# AFE_Buffer.net
KiCad netlist of a schematic drawn in Altium Designer
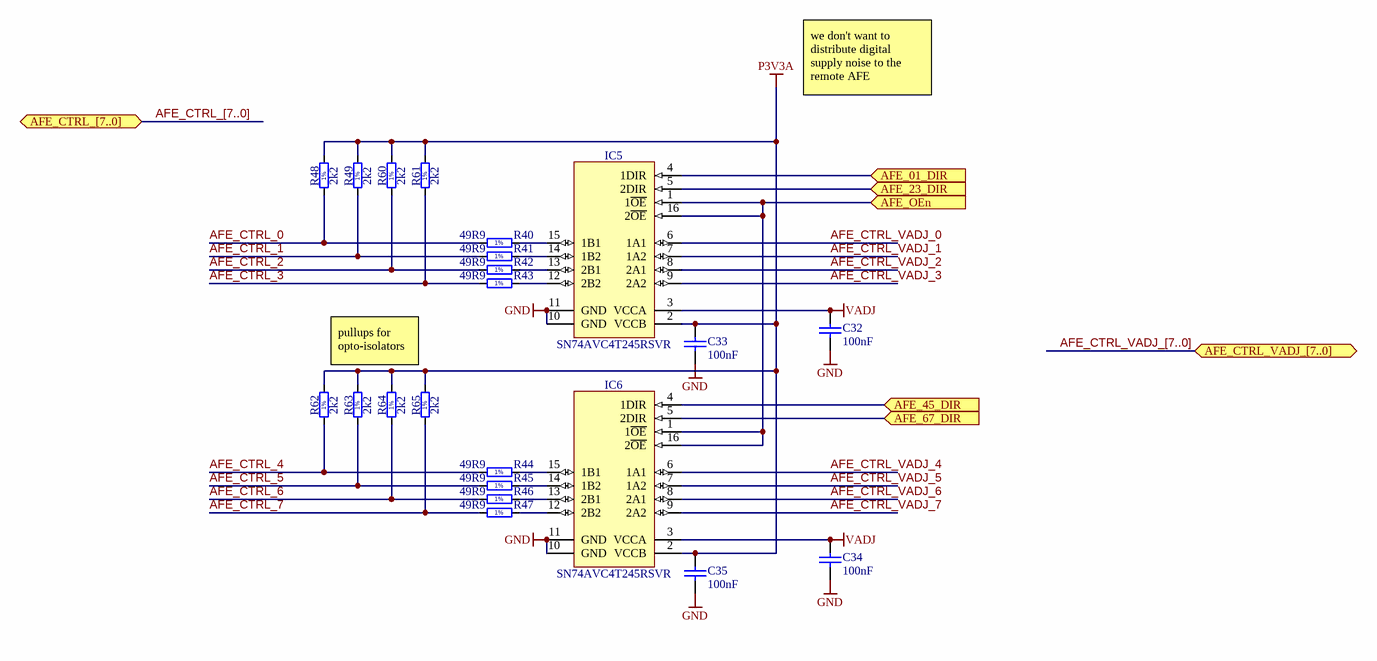
[diagram p0: AFE_Buffer.SchDoc]

(export (version "E")
  (design (tool "Eeschema 10.0.6"))
  (components
    (comp (ref "C32")
      (value "100nF")
      (footprint "CAPC1005X55N")
      (description "Non-polarised capacitor")
      (fields
        (field (name "PART NUMBER") "CC0402_100NF_16V_10%_X5R")
        (field (name "VOLTAGE") "16V")
        (field (name "AUTHOR") "CERN DEM JLC")
      )
      (libsource (lib "Capacitors") (part "Capacitor - non polarized"))
    )
    (comp (ref "C33")
      (value "100nF")
      (footprint "CAPC1005X55N")
      (description "Non-polarised capacitor")
      (fields
        (field (name "PART NUMBER") "CC0402_100NF_16V_10%_X5R")
        (field (name "VOLTAGE") "16V")
        (field (name "AUTHOR") "CERN DEM JLC")
      )
      (libsource (lib "Capacitors") (part "Capacitor - non polarized"))
    )
    (comp (ref "C34")
      (value "100nF")
      (footprint "CAPC1005X55N")
      (description "Non-polarised capacitor")
      (fields
        (field (name "PART NUMBER") "CC0402_100NF_16V_10%_X5R")
        (field (name "VOLTAGE") "16V")
        (field (name "AUTHOR") "CERN DEM JLC")
      )
      (libsource (lib "Capacitors") (part "Capacitor - non polarized"))
    )
    (comp (ref "C35")
      (value "100nF")
      (footprint "CAPC1005X55N")
      (description "Non-polarised capacitor")
      (fields
        (field (name "PART NUMBER") "CC0402_100NF_16V_10%_X5R")
        (field (name "VOLTAGE") "16V")
        (field (name "AUTHOR") "CERN DEM JLC")
      )
      (libsource (lib "Capacitors") (part "Capacitor - non polarized"))
    )
    (comp (ref "IC5")
      (value "SN74AVC4T245RSVR")
      (footprint "QFN40P180X260X55-16N")
      (description "4-Bit Dual-Supply Bus Transceiver with Configurable Voltage Translation and 3-State Output")
      (fields (field (name "MANUFACTURER") "TEXAS INSTRUMENTS") (field (name "AUTHOR") "CERN DEM JLC"))
      (libsource (lib "ICs And Semiconductors") (part "744T245_a"))
    )
    (comp (ref "IC6")
      (value "SN74AVC4T245RSVR")
      (footprint "QFN40P180X260X55-16N")
      (description "4-Bit Dual-Supply Bus Transceiver with Configurable Voltage Translation and 3-State Output")
      (fields (field (name "MANUFACTURER") "TEXAS INSTRUMENTS") (field (name "AUTHOR") "CERN DEM JLC"))
      (libsource (lib "ICs And Semiconductors") (part "744T245_a"))
    )
    (comp (ref "R40")
      (value "49R9")
      (footprint "RESC1005X40N")
      (description "Resistor - 1%")
      (fields
        (field (name "PART NUMBER") "R0402_49R9_1%_0.0625W_100PPM")
        (field (name "POWER") "0.0625W")
        (field (name "AUTHOR") "CERN DEM JLC")
      )
      (libsource (lib "Resistors") (part "Resistor - 1%"))
    )
    (comp (ref "R41")
      (value "49R9")
      (footprint "RESC1005X40N")
      (description "Resistor - 1%")
      (fields
        (field (name "PART NUMBER") "R0402_49R9_1%_0.0625W_100PPM")
        (field (name "POWER") "0.0625W")
        (field (name "AUTHOR") "CERN DEM JLC")
      )
      (libsource (lib "Resistors") (part "Resistor - 1%"))
    )
    (comp (ref "R42")
      (value "49R9")
      (footprint "RESC1005X40N")
      (description "Resistor - 1%")
      (fields
        (field (name "PART NUMBER") "R0402_49R9_1%_0.0625W_100PPM")
        (field (name "POWER") "0.0625W")
        (field (name "AUTHOR") "CERN DEM JLC")
      )
      (libsource (lib "Resistors") (part "Resistor - 1%"))
    )
    (comp (ref "R43")
      (value "49R9")
      (footprint "RESC1005X40N")
      (description "Resistor - 1%")
      (fields
        (field (name "PART NUMBER") "R0402_49R9_1%_0.0625W_100PPM")
        (field (name "POWER") "0.0625W")
        (field (name "AUTHOR") "CERN DEM JLC")
      )
      (libsource (lib "Resistors") (part "Resistor - 1%"))
    )
    (comp (ref "R44")
      (value "49R9")
      (footprint "RESC1005X40N")
      (description "Resistor - 1%")
      (fields
        (field (name "PART NUMBER") "R0402_49R9_1%_0.0625W_100PPM")
        (field (name "POWER") "0.0625W")
        (field (name "AUTHOR") "CERN DEM JLC")
      )
      (libsource (lib "Resistors") (part "Resistor - 1%"))
    )
    (comp (ref "R45")
      (value "49R9")
      (footprint "RESC1005X40N")
      (description "Resistor - 1%")
      (fields
        (field (name "PART NUMBER") "R0402_49R9_1%_0.0625W_100PPM")
        (field (name "POWER") "0.0625W")
        (field (name "AUTHOR") "CERN DEM JLC")
      )
      (libsource (lib "Resistors") (part "Resistor - 1%"))
    )
    (comp (ref "R46")
      (value "49R9")
      (footprint "RESC1005X40N")
      (description "Resistor - 1%")
      (fields
        (field (name "PART NUMBER") "R0402_49R9_1%_0.0625W_100PPM")
        (field (name "POWER") "0.0625W")
        (field (name "AUTHOR") "CERN DEM JLC")
      )
      (libsource (lib "Resistors") (part "Resistor - 1%"))
    )
    (comp (ref "R47")
      (value "49R9")
      (footprint "RESC1005X40N")
      (description "Resistor - 1%")
      (fields
        (field (name "PART NUMBER") "R0402_49R9_1%_0.0625W_100PPM")
        (field (name "POWER") "0.0625W")
        (field (name "AUTHOR") "CERN DEM JLC")
      )
      (libsource (lib "Resistors") (part "Resistor - 1%"))
    )
    (comp (ref "R48")
      (value "2k2")
      (footprint "RESC1005X40N")
      (description "Resistor - 1%")
      (fields
        (field (name "PART NUMBER") "R0402_2K2_1%_0.0625W_100PPM")
        (field (name "POWER") "0.0625W")
        (field (name "AUTHOR") "CERN DEM JLC")
      )
      (libsource (lib "Resistors") (part "Resistor - 1%"))
    )
    (comp (ref "R49")
      (value "2k2")
      (footprint "RESC1005X40N")
      (description "Resistor - 1%")
      (fields
        (field (name "PART NUMBER") "R0402_2K2_1%_0.0625W_100PPM")
        (field (name "POWER") "0.0625W")
        (field (name "AUTHOR") "CERN DEM JLC")
      )
      (libsource (lib "Resistors") (part "Resistor - 1%"))
    )
    (comp (ref "R60")
      (value "2k2")
      (footprint "RESC1005X40N")
      (description "Resistor - 1%")
      (fields
        (field (name "PART NUMBER") "R0402_2K2_1%_0.0625W_100PPM")
        (field (name "POWER") "0.0625W")
        (field (name "AUTHOR") "CERN DEM JLC")
      )
      (libsource (lib "Resistors") (part "Resistor - 1%"))
    )
    (comp (ref "R61")
      (value "2k2")
      (footprint "RESC1005X40N")
      (description "Resistor - 1%")
      (fields
        (field (name "PART NUMBER") "R0402_2K2_1%_0.0625W_100PPM")
        (field (name "POWER") "0.0625W")
        (field (name "AUTHOR") "CERN DEM JLC")
      )
      (libsource (lib "Resistors") (part "Resistor - 1%"))
    )
    (comp (ref "R62")
      (value "2k2")
      (footprint "RESC1005X40N")
      (description "Resistor - 1%")
      (fields
        (field (name "PART NUMBER") "R0402_2K2_1%_0.0625W_100PPM")
        (field (name "POWER") "0.0625W")
        (field (name "AUTHOR") "CERN DEM JLC")
      )
      (libsource (lib "Resistors") (part "Resistor - 1%"))
    )
    (comp (ref "R63")
      (value "2k2")
      (footprint "RESC1005X40N")
      (description "Resistor - 1%")
      (fields
        (field (name "PART NUMBER") "R0402_2K2_1%_0.0625W_100PPM")
        (field (name "POWER") "0.0625W")
        (field (name "AUTHOR") "CERN DEM JLC")
      )
      (libsource (lib "Resistors") (part "Resistor - 1%"))
    )
    (comp (ref "R64")
      (value "2k2")
      (footprint "RESC1005X40N")
      (description "Resistor - 1%")
      (fields
        (field (name "PART NUMBER") "R0402_2K2_1%_0.0625W_100PPM")
        (field (name "POWER") "0.0625W")
        (field (name "AUTHOR") "CERN DEM JLC")
      )
      (libsource (lib "Resistors") (part "Resistor - 1%"))
    )
    (comp (ref "R65")
      (value "2k2")
      (footprint "RESC1005X40N")
      (description "Resistor - 1%")
      (fields
        (field (name "PART NUMBER") "R0402_2K2_1%_0.0625W_100PPM")
        (field (name "POWER") "0.0625W")
        (field (name "AUTHOR") "CERN DEM JLC")
      )
      (libsource (lib "Resistors") (part "Resistor - 1%"))
    )
  )
  (nets
    (net (code "1") (name "/AFE_01_DIR") (class "Default")
      (node (ref "IC5") (pin "4") (pinfunction "1DIR_4") (pintype "input"))
    )
    (net (code "2") (name "/AFE_23_DIR") (class "Default")
      (node (ref "IC5") (pin "5") (pinfunction "2DIR_5") (pintype "input"))
    )
    (net (code "3") (name "/AFE_45_DIR") (class "Default")
      (node (ref "IC6") (pin "4") (pinfunction "1DIR_4") (pintype "input"))
    )
    (net (code "4") (name "/AFE_67_DIR") (class "Default")
      (node (ref "IC6") (pin "5") (pinfunction "2DIR_5") (pintype "input"))
    )
    (net (code "5") (name "/AFE_CTRL_0") (class "Default")
      (node (ref "R40") (pin "1") (pinfunction "1_1") (pintype "passive"))
      (node (ref "R48") (pin "1") (pinfunction "1_1") (pintype "passive"))
    )
    (net (code "6") (name "/AFE_CTRL_1") (class "Default")
      (node (ref "R41") (pin "1") (pinfunction "1_1") (pintype "passive"))
      (node (ref "R49") (pin "1") (pinfunction "1_1") (pintype "passive"))
    )
    (net (code "7") (name "/AFE_CTRL_2") (class "Default")
      (node (ref "R42") (pin "1") (pinfunction "1_1") (pintype "passive"))
      (node (ref "R60") (pin "1") (pinfunction "1_1") (pintype "passive"))
    )
    (net (code "8") (name "/AFE_CTRL_3") (class "Default")
      (node (ref "R43") (pin "1") (pinfunction "1_1") (pintype "passive"))
      (node (ref "R61") (pin "1") (pinfunction "1_1") (pintype "passive"))
    )
    (net (code "9") (name "/AFE_CTRL_4") (class "Default")
      (node (ref "R44") (pin "1") (pinfunction "1_1") (pintype "passive"))
      (node (ref "R62") (pin "1") (pinfunction "1_1") (pintype "passive"))
    )
    (net (code "10") (name "/AFE_CTRL_5") (class "Default")
      (node (ref "R45") (pin "1") (pinfunction "1_1") (pintype "passive"))
      (node (ref "R63") (pin "1") (pinfunction "1_1") (pintype "passive"))
    )
    (net (code "11") (name "/AFE_CTRL_6") (class "Default")
      (node (ref "R46") (pin "1") (pinfunction "1_1") (pintype "passive"))
      (node (ref "R64") (pin "1") (pinfunction "1_1") (pintype "passive"))
    )
    (net (code "12") (name "/AFE_CTRL_7") (class "Default")
      (node (ref "R47") (pin "1") (pinfunction "1_1") (pintype "passive"))
      (node (ref "R65") (pin "1") (pinfunction "1_1") (pintype "passive"))
    )
    (net (code "13") (name "/AFE_CTRL_VADJ_0") (class "Default")
      (node (ref "IC5") (pin "6") (pinfunction "1A1_6") (pintype "bidirectional"))
    )
    (net (code "14") (name "/AFE_CTRL_VADJ_1") (class "Default")
      (node (ref "IC5") (pin "7") (pinfunction "1A2_7") (pintype "bidirectional"))
    )
    (net (code "15") (name "/AFE_CTRL_VADJ_2") (class "Default")
      (node (ref "IC5") (pin "8") (pinfunction "2A1_8") (pintype "bidirectional"))
    )
    (net (code "16") (name "/AFE_CTRL_VADJ_3") (class "Default")
      (node (ref "IC5") (pin "9") (pinfunction "2A2_9") (pintype "bidirectional"))
    )
    (net (code "17") (name "/AFE_CTRL_VADJ_4") (class "Default")
      (node (ref "IC6") (pin "6") (pinfunction "1A1_6") (pintype "bidirectional"))
    )
    (net (code "18") (name "/AFE_CTRL_VADJ_5") (class "Default")
      (node (ref "IC6") (pin "7") (pinfunction "1A2_7") (pintype "bidirectional"))
    )
    (net (code "19") (name "/AFE_CTRL_VADJ_6") (class "Default")
      (node (ref "IC6") (pin "8") (pinfunction "2A1_8") (pintype "bidirectional"))
    )
    (net (code "20") (name "/AFE_CTRL_VADJ_7") (class "Default")
      (node (ref "IC6") (pin "9") (pinfunction "2A2_9") (pintype "bidirectional"))
    )
    (net (code "23") (name "/AFE_OEn") (class "Default")
      (node (ref "IC5") (pin "1") (pinfunction "1~{OE}_1") (pintype "input"))
      (node (ref "IC5") (pin "16") (pinfunction "2~{OE}_16") (pintype "input"))
      (node (ref "IC6") (pin "1") (pinfunction "1~{OE}_1") (pintype "input"))
      (node (ref "IC6") (pin "16") (pinfunction "2~{OE}_16") (pintype "input"))
    )
    (net (code "24") (name "GND") (class "Default")
      (node (ref "C32") (pin "1") (pinfunction "1_1") (pintype "passive"))
      (node (ref "C33") (pin "1") (pinfunction "1_1") (pintype "passive"))
      (node (ref "C34") (pin "1") (pinfunction "1_1") (pintype "passive"))
      (node (ref "C35") (pin "1") (pinfunction "1_1") (pintype "passive"))
      (node (ref "IC5") (pin "10") (pinfunction "GND_10") (pintype "power_in"))
      (node (ref "IC5") (pin "11") (pinfunction "GND_11") (pintype "power_in"))
      (node (ref "IC6") (pin "10") (pinfunction "GND_10") (pintype "power_in"))
      (node (ref "IC6") (pin "11") (pinfunction "GND_11") (pintype "power_in"))
    )
    (net (code "25") (name "Net-(IC5-1B1)") (class "Default")
      (node (ref "IC5") (pin "15") (pinfunction "1B1_15") (pintype "bidirectional"))
      (node (ref "R40") (pin "2") (pinfunction "2_2") (pintype "passive"))
    )
    (net (code "26") (name "Net-(IC5-1B2)") (class "Default")
      (node (ref "IC5") (pin "14") (pinfunction "1B2_14") (pintype "bidirectional"))
      (node (ref "R41") (pin "2") (pinfunction "2_2") (pintype "passive"))
    )
    (net (code "27") (name "Net-(IC5-2B1)") (class "Default")
      (node (ref "IC5") (pin "13") (pinfunction "2B1_13") (pintype "bidirectional"))
      (node (ref "R42") (pin "2") (pinfunction "2_2") (pintype "passive"))
    )
    (net (code "28") (name "Net-(IC5-2B2)") (class "Default")
      (node (ref "IC5") (pin "12") (pinfunction "2B2_12") (pintype "bidirectional"))
      (node (ref "R43") (pin "2") (pinfunction "2_2") (pintype "passive"))
    )
    (net (code "29") (name "Net-(IC6-1B1)") (class "Default")
      (node (ref "IC6") (pin "15") (pinfunction "1B1_15") (pintype "bidirectional"))
      (node (ref "R44") (pin "2") (pinfunction "2_2") (pintype "passive"))
    )
    (net (code "30") (name "Net-(IC6-1B2)") (class "Default")
      (node (ref "IC6") (pin "14") (pinfunction "1B2_14") (pintype "bidirectional"))
      (node (ref "R45") (pin "2") (pinfunction "2_2") (pintype "passive"))
    )
    (net (code "31") (name "Net-(IC6-2B1)") (class "Default")
      (node (ref "IC6") (pin "13") (pinfunction "2B1_13") (pintype "bidirectional"))
      (node (ref "R46") (pin "2") (pinfunction "2_2") (pintype "passive"))
    )
    (net (code "32") (name "Net-(IC6-2B2)") (class "Default")
      (node (ref "IC6") (pin "12") (pinfunction "2B2_12") (pintype "bidirectional"))
      (node (ref "R47") (pin "2") (pinfunction "2_2") (pintype "passive"))
    )
    (net (code "33") (name "P3V3A") (class "Default")
      (node (ref "C33") (pin "2") (pinfunction "2_2") (pintype "passive"))
      (node (ref "C35") (pin "2") (pinfunction "2_2") (pintype "passive"))
      (node (ref "IC5") (pin "2") (pinfunction "VCCB_2") (pintype "power_in"))
      (node (ref "IC6") (pin "2") (pinfunction "VCCB_2") (pintype "power_in"))
      (node (ref "R48") (pin "2") (pinfunction "2_2") (pintype "passive"))
      (node (ref "R49") (pin "2") (pinfunction "2_2") (pintype "passive"))
      (node (ref "R60") (pin "2") (pinfunction "2_2") (pintype "passive"))
      (node (ref "R61") (pin "2") (pinfunction "2_2") (pintype "passive"))
      (node (ref "R62") (pin "2") (pinfunction "2_2") (pintype "passive"))
      (node (ref "R63") (pin "2") (pinfunction "2_2") (pintype "passive"))
      (node (ref "R64") (pin "2") (pinfunction "2_2") (pintype "passive"))
      (node (ref "R65") (pin "2") (pinfunction "2_2") (pintype "passive"))
    )
    (net (code "34") (name "VADJ") (class "Default")
      (node (ref "C32") (pin "2") (pinfunction "2_2") (pintype "passive"))
      (node (ref "C34") (pin "2") (pinfunction "2_2") (pintype "passive"))
      (node (ref "IC5") (pin "3") (pinfunction "VCCA_3") (pintype "power_in"))
      (node (ref "IC6") (pin "3") (pinfunction "VCCA_3") (pintype "power_in"))
    )
  )
)
